# Main.net
KiCad netlist of a schematic drawn in Altium Designer
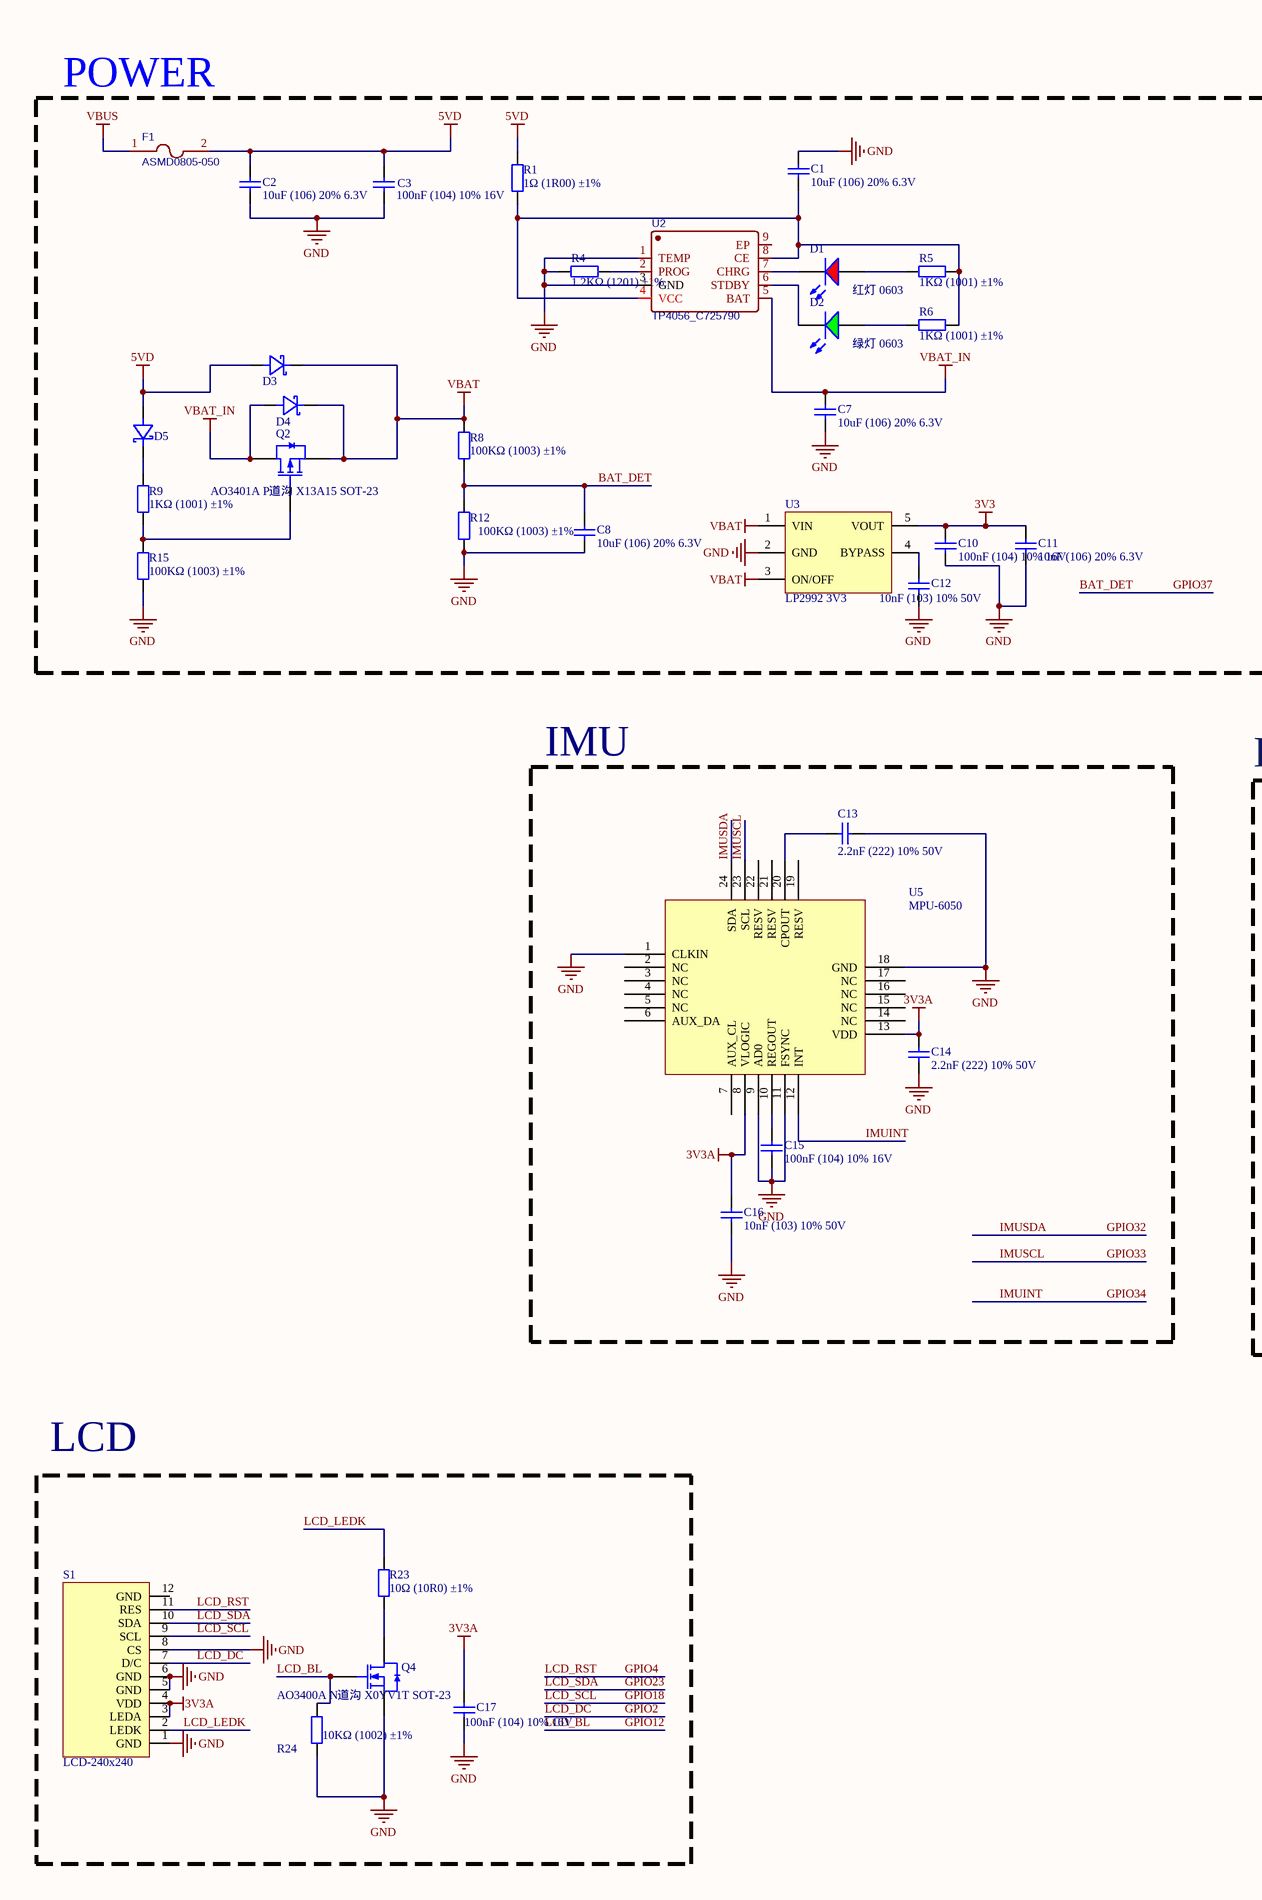
[diagram p0: Main.SchDoc, left]
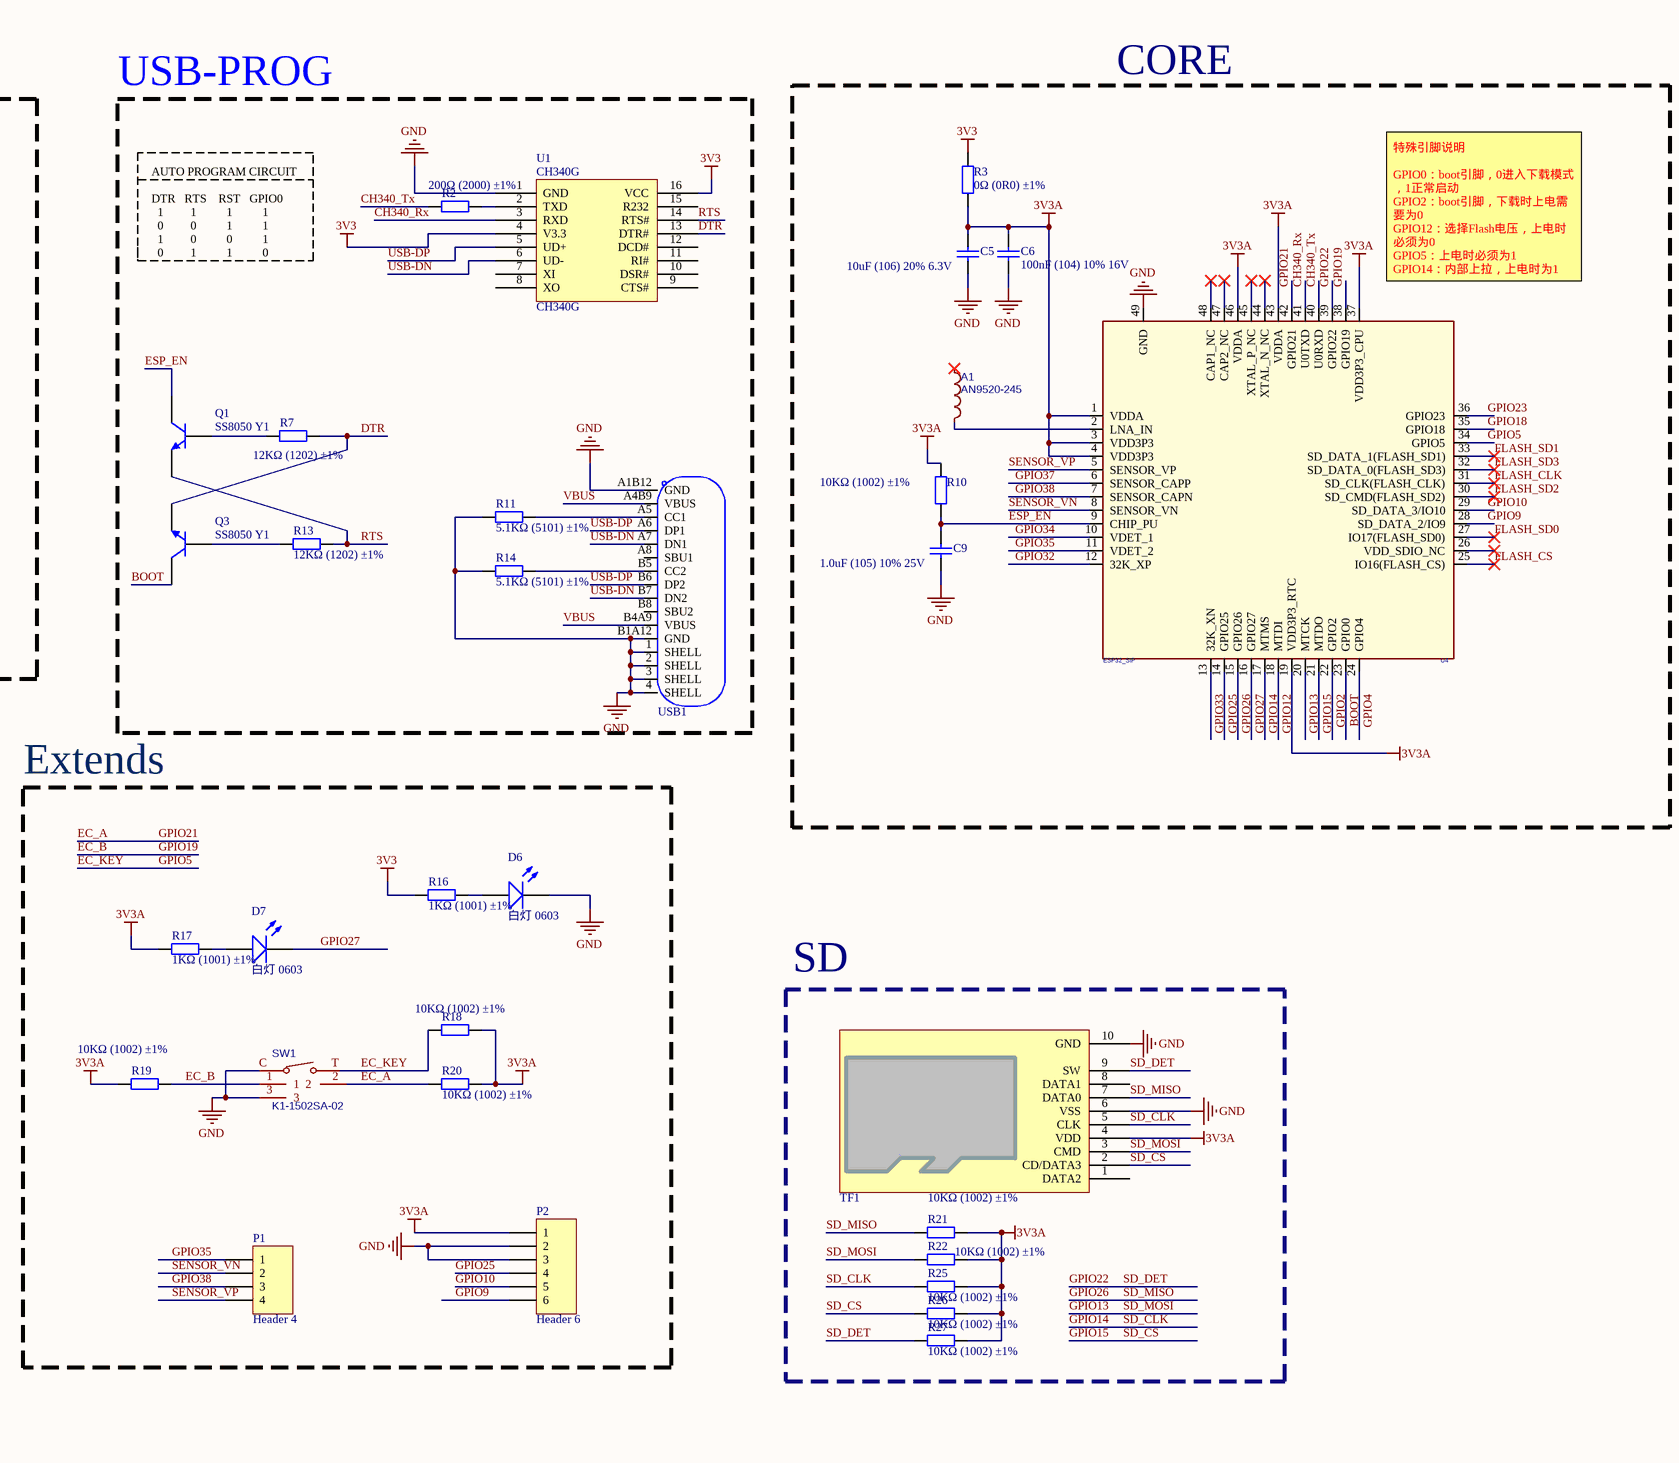
[diagram p1: Main.SchDoc, right]

(export (version "E")
  (design (tool "Eeschema 10.0.6"))
  (components
    (comp (ref "A1")
      (value "AN9520-245")
      (footprint "ANT-SMD_L9.5-W2.1")
      (description "陶瓷wifi/bt天线")
      (fields (field (name "BOM_SUPPLIER PART") "C99665"))
      (libsource (lib "mysch") (part "AN9520-245"))
    )
    (comp (ref "C1")
      (value "10uF (106) 20% 6.3V")
      (footprint "0402_C")
      (description "贴片电容")
      (libsource (lib "Miscellaneous Devices LC") (part "0402 10uF (106) 20% 6.3V"))
    )
    (comp (ref "C2")
      (value "10uF (106) 20% 6.3V")
      (footprint "0402_C")
      (description "贴片电容")
      (libsource (lib "Cap") (part "0402 10uF (106) 20% 6.3V"))
    )
    (comp (ref "C3")
      (value "100nF (104) 10% 16V")
      (footprint "0402_C")
      (description "贴片电容")
      (libsource (lib "Cap") (part "0402 100nF (104) 10% 16V"))
    )
    (comp (ref "C5")
      (value "10uF (106) 20% 6.3V")
      (footprint "0402_C")
      (description "贴片电容")
      (libsource (lib "Miscellaneous Devices LC") (part "0402 10uF (106) 20% 6.3V"))
    )
    (comp (ref "C6")
      (value "100nF (104) 10% 16V")
      (footprint "0402_C")
      (description "贴片电容")
      (libsource (lib "Miscellaneous Devices LC") (part "0402 100nF (104) 10% 16V"))
    )
    (comp (ref "C7")
      (value "10uF (106) 20% 6.3V")
      (footprint "0402_C")
      (description "贴片电容")
      (libsource (lib "Miscellaneous Devices LC") (part "0402 10uF (106) 20% 6.3V"))
    )
    (comp (ref "C8")
      (value "10uF (106) 20% 6.3V")
      (footprint "0402_C")
      (description "贴片电容")
      (libsource (lib "Miscellaneous Devices LC") (part "0402 10uF (106) 20% 6.3V"))
    )
    (comp (ref "C9")
      (value "1.0uF (105) 10% 25V")
      (footprint "0402_C")
      (description "贴片电容")
      (libsource (lib "Miscellaneous Devices LC") (part "0402 1.0uF (105) 10% 25V"))
    )
    (comp (ref "C10")
      (value "100nF (104) 10% 16V")
      (footprint "0402_C")
      (description "贴片电容")
      (libsource (lib "Miscellaneous Devices LC") (part "0402 100nF (104) 10% 16V"))
    )
    (comp (ref "C11")
      (value "10uF (106) 20% 6.3V")
      (footprint "0402_C")
      (description "贴片电容")
      (libsource (lib "Miscellaneous Devices LC") (part "0402 10uF (106) 20% 6.3V"))
    )
    (comp (ref "C12")
      (value "10nF (103) 10% 50V")
      (footprint "0402_C")
      (description "贴片电容")
      (libsource (lib "Miscellaneous Devices LC") (part "0402 10nF (103) 10% 50V"))
    )
    (comp (ref "C13")
      (value "2.2nF (222) 10% 50V")
      (footprint "0402_C")
      (description "贴片电容")
      (libsource (lib "Cap") (part "0402 2.2nF (222) 10% 50V"))
    )
    (comp (ref "C14")
      (value "2.2nF (222) 10% 50V")
      (footprint "0402_C")
      (description "贴片电容")
      (libsource (lib "Cap") (part "0402 2.2nF (222) 10% 50V"))
    )
    (comp (ref "C15")
      (value "100nF (104) 10% 16V")
      (footprint "0402_C")
      (description "贴片电容")
      (libsource (lib "Cap") (part "0402 100nF (104) 10% 16V"))
    )
    (comp (ref "C16")
      (value "10nF (103) 10% 50V")
      (footprint "0402_C")
      (description "贴片电容")
      (libsource (lib "Cap") (part "0402 10nF (103) 10% 50V"))
    )
    (comp (ref "C17")
      (value "100nF (104) 10% 16V")
      (footprint "0402_C")
      (description "贴片电容")
      (libsource (lib "Miscellaneous Devices LC") (part "0402 100nF (104) 10% 16V"))
    )
    (comp (ref "D1")
      (value "红灯 0603")
      (footprint "0603_LED_S1")
      (description "发光二极管")
      (libsource (lib "Miscellaneous Devices LC") (part "0603 红灯"))
    )
    (comp (ref "D2")
      (value "绿灯 0603")
      (footprint "0603_LED_S1")
      (description "发光二极管")
      (libsource (lib "Miscellaneous Devices LC") (part "0603 绿灯"))
    )
    (comp (ref "D3")
      (value "1N5819W")
      (footprint "SOD-123")
      (description "二极管")
      (fields (field (name "MANUFACTURER") "TWGMC(台湾迪嘉)"))
      (libsource (lib "mysch") (part "1N5819W"))
    )
    (comp (ref "D4")
      (value "1N5819W")
      (footprint "SOD-123")
      (description "二极管")
      (fields (field (name "MANUFACTURER") "TWGMC(台湾迪嘉)"))
      (libsource (lib "mysch") (part "1N5819W"))
    )
    (comp (ref "D5")
      (value "1N5819W")
      (footprint "SOD-123")
      (description "二极管")
      (fields (field (name "MANUFACTURER") "TWGMC(台湾迪嘉)"))
      (libsource (lib "mysch") (part "1N5819W"))
    )
    (comp (ref "D6")
      (value "白灯 0603")
      (footprint "0603_LED_S1")
      (description "发光二极管")
      (libsource (lib "Miscellaneous Devices LC") (part "0603 白灯"))
    )
    (comp (ref "D7")
      (value "白灯 0603")
      (footprint "0603_LED_S1")
      (description "发光二极管")
      (libsource (lib "Miscellaneous Devices LC") (part "0603 白灯"))
    )
    (comp (ref "F1")
      (value "ASMD0805-050")
      (footprint "ASMD0805")
      (fields (field (name "BOM_SUPPLIER PART") "C135329") (field (name "CONTRIBUTOR") "LCSC"))
      (libsource (lib "mysch") (part "ASMD0805-050"))
    )
    (comp (ref "P1")
      (value "Header 4")
      (footprint "HDR1X4")
      (description "Header, 4-Pin")
      (fields (field (name "PUBLISHER") "Altium Limited"))
      (libsource (lib "Miscellaneous Connectors") (part "Header 4"))
    )
    (comp (ref "P2")
      (value "Header 6")
      (footprint "HDR1X6")
      (description "Header, 6-Pin")
      (fields (field (name "PUBLISHER") "Altium Limited"))
      (libsource (lib "Miscellaneous Connectors") (part "Header 6"))
    )
    (comp (ref "Q1")
      (value "SS8050 Y1")
      (footprint "SOT-23(SOT-23-3)")
      (description "三极管")
      (libsource (lib "Miscellaneous Devices LC") (part "SOT-23 SS8050 Y1"))
    )
    (comp (ref "Q2")
      (value "AO3401A P道沟 X13A15 SOT-23")
      (footprint "SOT-23-3L")
      (description "MOS(场效应管)")
      (libsource (lib "Miscellaneous Devices LC") (part "AO3401A P道沟 X13A15 SOT-23"))
    )
    (comp (ref "Q3")
      (value "SS8050 Y1")
      (footprint "SOT-23(SOT-23-3)")
      (description "三极管")
      (libsource (lib "Miscellaneous Devices LC") (part "SOT-23 SS8050 Y1"))
    )
    (comp (ref "Q4")
      (value "AO3400A N道沟 X0YV1T SOT-23")
      (footprint "SOT-23-3L")
      (description "MOS(场效应管)")
      (libsource (lib "Miscellaneous Devices LC") (part "AO3400A N道沟 X0YV1T SOT-23"))
    )
    (comp (ref "R1")
      (value "1Ω (1R00) ±1%")
      (footprint "0402_R")
      (description "贴片电阻")
      (libsource (lib "Miscellaneous Devices LC") (part "0402 1Ω (1R00) 1%"))
    )
    (comp (ref "R2")
      (value "200Ω (2000) ±1%")
      (footprint "0402_R")
      (description "贴片电阻")
      (libsource (lib "Miscellaneous Devices LC") (part "0402 200Ω (2000) 1%"))
    )
    (comp (ref "R3")
      (value "0Ω (0R0) ±1%")
      (footprint "0402_R")
      (description "贴片电阻")
      (libsource (lib "Miscellaneous Devices LC") (part "0402 0Ω (0R0) 1%"))
    )
    (comp (ref "R4")
      (value "1.2KΩ (1201) ±1%")
      (footprint "0402_R")
      (description "贴片电阻")
      (libsource (lib "Miscellaneous Devices LC") (part "0402 1.2KΩ (1201) 1%"))
    )
    (comp (ref "R5")
      (value "1KΩ (1001) ±1%")
      (footprint "0402_R")
      (description "贴片电阻")
      (libsource (lib "") (part "0402 1KΩ (1001) 1%_1"))
    )
    (comp (ref "R6")
      (value "1KΩ (1001) ±1%")
      (footprint "0402_R")
      (description "贴片电阻")
      (libsource (lib "") (part "0402 1KΩ (1001) 1%_1"))
    )
    (comp (ref "R7")
      (value "12KΩ (1202) ±1%")
      (footprint "0402_R")
      (description "贴片电阻")
      (libsource (lib "RES") (part "0402 12KΩ (1202) 1%"))
    )
    (comp (ref "R8")
      (value "100KΩ (1003) ±1%")
      (footprint "0402_R")
      (description "贴片电阻")
      (libsource (lib "Miscellaneous Devices LC") (part "0402 100KΩ (1003) 1%"))
    )
    (comp (ref "R9")
      (value "1KΩ (1001) ±1%")
      (footprint "0402_R")
      (description "贴片电阻")
      (libsource (lib "Miscellaneous Devices LC") (part "0402 1KΩ (1001) 1%"))
    )
    (comp (ref "R10")
      (value "10KΩ (1002) ±1%")
      (footprint "0402_R")
      (description "贴片电阻")
      (libsource (lib "") (part "0402 10KΩ (1002) 1%_1"))
    )
    (comp (ref "R11")
      (value "5.1KΩ (5101) ±1%")
      (footprint "0402_R")
      (description "贴片电阻")
      (libsource (lib "RES") (part "0402 5.1KΩ (5101) 1%"))
    )
    (comp (ref "R12")
      (value "100KΩ (1003) ±1%")
      (footprint "0402_R")
      (description "贴片电阻")
      (libsource (lib "Miscellaneous Devices LC") (part "0402 100KΩ (1003) 1%"))
    )
    (comp (ref "R13")
      (value "12KΩ (1202) ±1%")
      (footprint "0402_R")
      (description "贴片电阻")
      (libsource (lib "RES") (part "0402 12KΩ (1202) 1%"))
    )
    (comp (ref "R14")
      (value "5.1KΩ (5101) ±1%")
      (footprint "0402_R")
      (description "贴片电阻")
      (libsource (lib "RES") (part "0402 5.1KΩ (5101) 1%"))
    )
    (comp (ref "R15")
      (value "100KΩ (1003) ±1%")
      (footprint "0402_R")
      (description "贴片电阻")
      (libsource (lib "Miscellaneous Devices LC") (part "0402 100KΩ (1003) 1%"))
    )
    (comp (ref "R16")
      (value "1KΩ (1001) ±1%")
      (footprint "0402_R")
      (description "贴片电阻")
      (libsource (lib "RES") (part "0402 1KΩ (1001) 1%"))
    )
    (comp (ref "R17")
      (value "1KΩ (1001) ±1%")
      (footprint "0402_R")
      (description "贴片电阻")
      (libsource (lib "RES") (part "0402 1KΩ (1001) 1%"))
    )
    (comp (ref "R18")
      (value "10KΩ (1002) ±1%")
      (footprint "0402_R")
      (description "贴片电阻")
      (libsource (lib "Miscellaneous Devices LC") (part "0402 10KΩ (1002) 1%"))
    )
    (comp (ref "R19")
      (value "10KΩ (1002) ±1%")
      (footprint "0402_R")
      (description "贴片电阻")
      (libsource (lib "Miscellaneous Devices LC") (part "0402 10KΩ (1002) 1%"))
    )
    (comp (ref "R20")
      (value "10KΩ (1002) ±1%")
      (footprint "0402_R")
      (description "贴片电阻")
      (libsource (lib "Miscellaneous Devices LC") (part "0402 10KΩ (1002) 1%"))
    )
    (comp (ref "R21")
      (value "10KΩ (1002) ±1%")
      (footprint "0402_R")
      (description "贴片电阻")
      (libsource (lib "Miscellaneous Devices LC") (part "0402 10KΩ (1002) 1%"))
    )
    (comp (ref "R22")
      (value "10KΩ (1002) ±1%")
      (footprint "0402_R")
      (description "贴片电阻")
      (libsource (lib "Miscellaneous Devices LC") (part "0402 10KΩ (1002) 1%"))
    )
    (comp (ref "R23")
      (value "10Ω (10R0) ±1%")
      (footprint "0402_R")
      (description "贴片电阻")
      (libsource (lib "Miscellaneous Devices LC") (part "0402 10Ω (10R0) 1%"))
    )
    (comp (ref "R24")
      (value "10KΩ (1002) ±1%")
      (footprint "0402_R")
      (description "贴片电阻")
      (libsource (lib "") (part "0402 10KΩ (1002) 1%_1"))
    )
    (comp (ref "R25")
      (value "10KΩ (1002) ±1%")
      (footprint "0402_R")
      (description "贴片电阻")
      (libsource (lib "Miscellaneous Devices LC") (part "0402 10KΩ (1002) 1%"))
    )
    (comp (ref "R26")
      (value "10KΩ (1002) ±1%")
      (footprint "0402_R")
      (description "贴片电阻")
      (libsource (lib "Miscellaneous Devices LC") (part "0402 10KΩ (1002) 1%"))
    )
    (comp (ref "R27")
      (value "10KΩ (1002) ±1%")
      (footprint "0402_R")
      (description "贴片电阻")
      (libsource (lib "Miscellaneous Devices LC") (part "0402 10KΩ (1002) 1%"))
    )
    (comp (ref "S1")
      (value "LCD-240x240")
      (footprint "LCD-240x240-FlUSH-154")
      (description "显示屏")
      (libsource (lib "mLib") (part "LCD-240x240"))
    )
    (comp (ref "SW1")
      (value "K1-1502SA-02")
      (footprint "KEY-SMD_K1-1502SA-02")
      (description "拨码开关")
      (fields (field (name "BOM_SUPPLIER PART") "C128929") (field (name "CONTRIBUTOR") "LCSC"))
      (libsource (lib "mysch") (part "K1-1502SA-02"))
    )
    (comp (ref "TF1")
      (value "TF")
      (footprint "TF-SMD_THD2528")
      (description "8脚自弹")
      (libsource (lib "mysch") (part "TF卡座"))
    )
    (comp (ref "U1")
      (value "CH340G")
      (footprint "SOIC-16_150mil")
      (description "USB")
      (libsource (lib "Miscellaneous Devices LC") (part "CH340G_[C14267]"))
    )
    (comp (ref "U2")
      (value "TP4056_C725790")
      (footprint "ESOP-8_TP4056")
      (fields
        (field (name "BOM_SUPPLIER PART") "C725790")
        (field (name "BOM_MANUFACTURER PART") "TP4056")
        (field (name "CONTRIBUTOR") "LCSC")
      )
      (libsource (lib "mysch") (part "TP4056"))
    )
    (comp (ref "U3")
      (value "LP2992 3V3")
      (footprint "SOT-23-5_L3.0-W1.7-P0.95-LS2.8-BL")
      (description "LDO")
      (libsource (lib "mLib") (part "LP2992"))
    )
    (comp (ref "U4")
      (value "ESP32_SIP")
      (footprint "QFN-48_7X7")
      (libsource (lib "mLib") (part "ESP32-PICO"))
    )
    (comp (ref "U5")
      (value "MPU-6050")
      (footprint "QFN-24_4x4x05P")
      (description "传感器")
      (libsource (lib "IC") (part "MPU-6050_[C24112]"))
    )
    (comp (ref "USB1")
      (value "TYPE-C16PIN")
      (footprint "TYPE-C-SMD")
      (fields (field (name "MANUFACTURER") "SHOU HAN(首韩)"))
      (libsource (lib "mysch") (part "TYPE-C16PIN"))
    )
  )
  (nets
    (net (code "1") (name "/BAT_DET") (class "Default")
      (node (ref "C8") (pin "2") (pinfunction "2_2") (pintype "passive"))
      (node (ref "R12") (pin "2") (pinfunction "2_2") (pintype "passive"))
      (node (ref "R8") (pin "1") (pinfunction "1_1") (pintype "passive"))
      (node (ref "U4") (pin "6") (pinfunction "SENSOR_CAPP_6") (pintype "passive"))
    )
    (net (code "2") (name "/BOOT") (class "Default")
      (node (ref "Q3") (pin "3") (pinfunction "C_3") (pintype "passive"))
      (node (ref "U4") (pin "23") (pinfunction "GPIO0_23") (pintype "passive"))
    )
    (net (code "3") (name "/CH340_Rx") (class "Default")
      (node (ref "U1") (pin "3") (pinfunction "RXD_3") (pintype "passive"))
      (node (ref "U4") (pin "41") (pinfunction "U0TXD_41") (pintype "power_in"))
    )
    (net (code "4") (name "/CH340_Tx") (class "Default")
      (node (ref "R2") (pin "1") (pinfunction "1_1") (pintype "passive"))
      (node (ref "U4") (pin "40") (pinfunction "U0RXD_40") (pintype "power_in"))
    )
    (net (code "5") (name "/DTR") (class "Default")
      (node (ref "Q3") (pin "2") (pinfunction "E_2") (pintype "passive"))
      (node (ref "R7") (pin "2") (pinfunction "2_2") (pintype "passive"))
      (node (ref "U1") (pin "13") (pinfunction "DTR#_13") (pintype "passive"))
    )
    (net (code "6") (name "/EC_A") (class "Default")
      (node (ref "R20") (pin "1") (pinfunction "1_1") (pintype "passive"))
      (node (ref "SW1") (pin "2") (pinfunction "2_2") (pintype "passive"))
      (node (ref "U4") (pin "42") (pinfunction "GPIO21_42") (pintype "passive"))
    )
    (net (code "7") (name "/EC_B") (class "Default")
      (node (ref "R19") (pin "2") (pinfunction "2_2") (pintype "passive"))
      (node (ref "SW1") (pin "1") (pinfunction "1_1") (pintype "passive"))
      (node (ref "U4") (pin "38") (pinfunction "GPIO19_38") (pintype "passive"))
    )
    (net (code "8") (name "/EC_KEY") (class "Default")
      (node (ref "R18") (pin "1") (pinfunction "1_1") (pintype "passive"))
      (node (ref "SW1") (pin "T") (pinfunction "T_T") (pintype "passive"))
      (node (ref "U4") (pin "34") (pinfunction "GPIO5_34") (pintype "passive"))
    )
    (net (code "9") (name "/ESP_EN") (class "Default")
      (node (ref "C9") (pin "2") (pinfunction "2_2") (pintype "passive"))
      (node (ref "Q1") (pin "3") (pinfunction "C_3") (pintype "passive"))
      (node (ref "R10") (pin "1") (pinfunction "1_1") (pintype "passive"))
      (node (ref "U4") (pin "9") (pinfunction "CHIP_PU_9") (pintype "passive"))
    )
    (net (code "10") (name "/FLASH_CLK") (class "Default")
      (node (ref "U4") (pin "31") (pinfunction "SD_CLK(FLASH_CLK)_31") (pintype "passive+no_connect"))
    )
    (net (code "11") (name "/FLASH_CS") (class "Default")
      (node (ref "U4") (pin "25") (pinfunction "IO16(FLASH_CS)_25") (pintype "passive+no_connect"))
    )
    (net (code "12") (name "/FLASH_SD0") (class "Default")
      (node (ref "U4") (pin "27") (pinfunction "IO17(FLASH_SD0)_27") (pintype "passive+no_connect"))
    )
    (net (code "13") (name "/FLASH_SD1") (class "Default")
      (node (ref "U4") (pin "33") (pinfunction "SD_DATA_1(FLASH_SD1)_33") (pintype "passive+no_connect"))
    )
    (net (code "14") (name "/FLASH_SD2") (class "Default")
      (node (ref "U4") (pin "30") (pinfunction "SD_CMD(FLASH_SD2)_30") (pintype "passive+no_connect"))
    )
    (net (code "15") (name "/FLASH_SD3") (class "Default")
      (node (ref "U4") (pin "32") (pinfunction "SD_DATA_0(FLASH_SD3)_32") (pintype "passive+no_connect"))
    )
    (net (code "16") (name "/GPIO2") (class "Default")
      (node (ref "S1") (pin "7") (pinfunction "D/C_7") (pintype "passive"))
      (node (ref "U4") (pin "22") (pinfunction "GPIO2_22") (pintype "passive"))
    )
    (net (code "17") (name "/GPIO4") (class "Default")
      (node (ref "S1") (pin "11") (pinfunction "RES_11") (pintype "passive"))
      (node (ref "U4") (pin "24") (pinfunction "GPIO4_24") (pintype "passive"))
    )
    (net (code "18") (name "/GPIO9") (class "Default")
      (node (ref "P2") (pin "6") (pinfunction "6_6") (pintype "passive"))
      (node (ref "U4") (pin "28") (pinfunction "SD_DATA_2/IO9_28") (pintype "passive"))
    )
    (net (code "19") (name "/GPIO10") (class "Default")
      (node (ref "P2") (pin "5") (pinfunction "5_5") (pintype "passive"))
      (node (ref "U4") (pin "29") (pinfunction "SD_DATA_3/IO10_29") (pintype "passive"))
    )
    (net (code "20") (name "/GPIO12") (class "Default")
      (node (ref "Q4") (pin "1") (pinfunction "G_1") (pintype "passive"))
      (node (ref "R24") (pin "2") (pinfunction "2_2") (pintype "passive"))
      (node (ref "U4") (pin "18") (pinfunction "MTDI_18") (pintype "passive"))
    )
    (net (code "21") (name "/GPIO13") (class "Default")
      (node (ref "R22") (pin "1") (pinfunction "1_1") (pintype "passive"))
      (node (ref "TF1") (pin "3") (pinfunction "CMD_3") (pintype "passive"))
      (node (ref "U4") (pin "20") (pinfunction "MTCK_20") (pintype "passive"))
    )
    (net (code "22") (name "/GPIO14") (class "Default")
      (node (ref "R25") (pin "1") (pinfunction "1_1") (pintype "passive"))
      (node (ref "TF1") (pin "5") (pinfunction "CLK_5") (pintype "passive"))
      (node (ref "U4") (pin "17") (pinfunction "MTMS_17") (pintype "passive"))
    )
    (net (code "23") (name "/GPIO15") (class "Default")
      (node (ref "R26") (pin "1") (pinfunction "1_1") (pintype "passive"))
      (node (ref "TF1") (pin "2") (pinfunction "CD/DATA3_2") (pintype "passive"))
      (node (ref "U4") (pin "21") (pinfunction "MTDO_21") (pintype "passive"))
    )
    (net (code "24") (name "/GPIO18") (class "Default")
      (node (ref "S1") (pin "9") (pinfunction "SCL_9") (pintype "passive"))
      (node (ref "U4") (pin "35") (pinfunction "GPIO18_35") (pintype "passive"))
    )
    (net (code "25") (name "/GPIO22") (class "Default")
      (node (ref "R27") (pin "1") (pinfunction "1_1") (pintype "passive"))
      (node (ref "TF1") (pin "9") (pinfunction "SW_9") (pintype "passive"))
      (node (ref "U4") (pin "39") (pinfunction "GPIO22_39") (pintype "passive"))
    )
    (net (code "26") (name "/GPIO23") (class "Default")
      (node (ref "S1") (pin "10") (pinfunction "SDA_10") (pintype "passive"))
      (node (ref "U4") (pin "36") (pinfunction "GPIO23_36") (pintype "passive"))
    )
    (net (code "27") (name "/GPIO25") (class "Default")
      (node (ref "P2") (pin "4") (pinfunction "4_4") (pintype "passive"))
      (node (ref "U4") (pin "14") (pinfunction "GPIO25_14") (pintype "passive"))
    )
    (net (code "28") (name "/GPIO26") (class "Default")
      (node (ref "R21") (pin "1") (pinfunction "1_1") (pintype "passive"))
      (node (ref "TF1") (pin "7") (pinfunction "DATA0_7") (pintype "passive"))
      (node (ref "U4") (pin "15") (pinfunction "GPIO26_15") (pintype "passive"))
    )
    (net (code "29") (name "/GPIO27") (class "Default")
      (node (ref "D7") (pin "K") (pinfunction "K_K") (pintype "passive"))
      (node (ref "U4") (pin "16") (pinfunction "GPIO27_16") (pintype "passive"))
    )
    (net (code "30") (name "/GPIO32") (class "Default")
      (node (ref "U4") (pin "12") (pinfunction "32K_XP_12") (pintype "passive"))
      (node (ref "U5") (pin "24") (pinfunction "SDA_24") (pintype "passive"))
    )
    (net (code "31") (name "/GPIO33") (class "Default")
      (node (ref "U4") (pin "13") (pinfunction "32K_XN_13") (pintype "passive"))
      (node (ref "U5") (pin "23") (pinfunction "SCL_23") (pintype "passive"))
    )
    (net (code "32") (name "/GPIO34") (class "Default")
      (node (ref "U4") (pin "10") (pinfunction "VDET_1_10") (pintype "passive"))
      (node (ref "U5") (pin "12") (pinfunction "INT_12") (pintype "passive"))
    )
    (net (code "33") (name "/GPIO35") (class "Default")
      (node (ref "P1") (pin "1") (pinfunction "1_1") (pintype "passive"))
      (node (ref "U4") (pin "11") (pinfunction "VDET_2_11") (pintype "passive"))
    )
    (net (code "34") (name "/GPIO38") (class "Default")
      (node (ref "P1") (pin "3") (pinfunction "3_3") (pintype "passive"))
      (node (ref "U4") (pin "7") (pinfunction "SENSOR_CAPN_7") (pintype "passive"))
    )
    (net (code "35") (name "/LCD_LEDK") (class "Default")
      (node (ref "R23") (pin "2") (pinfunction "2_2") (pintype "passive"))
      (node (ref "S1") (pin "2") (pinfunction "LEDK_2") (pintype "passive"))
    )
    (net (code "36") (name "/RTS") (class "Default")
      (node (ref "Q1") (pin "2") (pinfunction "E_2") (pintype "passive"))
      (node (ref "R13") (pin "2") (pinfunction "2_2") (pintype "passive"))
      (node (ref "U1") (pin "14") (pinfunction "RTS#_14") (pintype "passive"))
    )
    (net (code "37") (name "/SENSOR_VN") (class "Default")
      (node (ref "P1") (pin "2") (pinfunction "2_2") (pintype "passive"))
      (node (ref "U4") (pin "8") (pinfunction "SENSOR_VN_8") (pintype "passive"))
    )
    (net (code "38") (name "/SENSOR_VP") (class "Default")
      (node (ref "P1") (pin "4") (pinfunction "4_4") (pintype "passive"))
      (node (ref "U4") (pin "5") (pinfunction "SENSOR_VP_5") (pintype "passive"))
    )
    (net (code "39") (name "/USB-DN") (class "Default")
      (node (ref "U1") (pin "6") (pinfunction "UD-_6") (pintype "passive"))
      (node (ref "USB1") (pin "A7") (pinfunction "DN1_A7") (pintype "passive"))
      (node (ref "USB1") (pin "B7") (pinfunction "DN2_B7") (pintype "passive"))
    )
    (net (code "40") (name "/USB-DP") (class "Default")
      (node (ref "U1") (pin "5") (pinfunction "UD+_5") (pintype "passive"))
      (node (ref "USB1") (pin "A6") (pinfunction "DP1_A6") (pintype "passive"))
      (node (ref "USB1") (pin "B6") (pinfunction "DP2_B6") (pintype "passive"))
    )
    (net (code "41") (name "3V3") (class "Default")
      (node (ref "C10") (pin "2") (pinfunction "2_2") (pintype "passive"))
      (node (ref "C11") (pin "2") (pinfunction "2_2") (pintype "passive"))
      (node (ref "R16") (pin "1") (pinfunction "1_1") (pintype "passive"))
      (node (ref "R3") (pin "2") (pinfunction "2_2") (pintype "passive"))
      (node (ref "U1") (pin "16") (pinfunction "VCC_16") (pintype "passive"))
      (node (ref "U1") (pin "4") (pinfunction "V3.3_4") (pintype "passive"))
      (node (ref "U3") (pin "5") (pinfunction "VOUT_5") (pintype "passive"))
    )
    (net (code "42") (name "3V3A") (class "Default")
      (node (ref "C14") (pin "2") (pinfunction "2_2") (pintype "passive"))
      (node (ref "C16") (pin "2") (pinfunction "2_2") (pintype "passive"))
      (node (ref "C17") (pin "2") (pinfunction "2_2") (pintype "passive"))
      (node (ref "C5") (pin "2") (pinfunction "2_2") (pintype "passive"))
      (node (ref "C6") (pin "2") (pinfunction "2_2") (pintype "passive"))
      (node (ref "P2") (pin "1") (pinfunction "1_1") (pintype "passive"))
      (node (ref "R10") (pin "2") (pinfunction "2_2") (pintype "passive"))
      (node (ref "R17") (pin "1") (pinfunction "1_1") (pintype "passive"))
      (node (ref "R18") (pin "2") (pinfunction "2_2") (pintype "passive"))
      (node (ref "R19") (pin "1") (pinfunction "1_1") (pintype "passive"))
      (node (ref "R20") (pin "2") (pinfunction "2_2") (pintype "passive"))
      (node (ref "R21") (pin "2") (pinfunction "2_2") (pintype "passive"))
      (node (ref "R22") (pin "2") (pinfunction "2_2") (pintype "passive"))
      (node (ref "R25") (pin "2") (pinfunction "2_2") (pintype "passive"))
      (node (ref "R26") (pin "2") (pinfunction "2_2") (pintype "passive"))
      (node (ref "R27") (pin "2") (pinfunction "2_2") (pintype "passive"))
      (node (ref "R3") (pin "1") (pinfunction "1_1") (pintype "passive"))
      (node (ref "S1") (pin "3") (pinfunction "LEDA_3") (pintype "passive"))
      (node (ref "S1") (pin "4") (pinfunction "VDD_4") (pintype "passive"))
      (node (ref "TF1") (pin "4") (pinfunction "VDD_4") (pintype "passive"))
      (node (ref "U4") (pin "1") (pinfunction "VDDA_1") (pintype "power_in"))
      (node (ref "U4") (pin "19") (pinfunction "VDD3P3_RTC_19") (pintype "power_in"))
      (node (ref "U4") (pin "3") (pinfunction "VDD3P3_3") (pintype "power_in"))
      (node (ref "U4") (pin "37") (pinfunction "VDD3P3_CPU_37") (pintype "power_in"))
      (node (ref "U4") (pin "4") (pinfunction "VDD3P3_4") (pintype "power_in"))
      (node (ref "U4") (pin "43") (pinfunction "VDDA_43") (pintype "power_in"))
      (node (ref "U4") (pin "46") (pinfunction "VDDA_46") (pintype "power_in"))
      (node (ref "U5") (pin "13") (pinfunction "VDD_13") (pintype "passive"))
      (node (ref "U5") (pin "8") (pinfunction "VLOGIC_8") (pintype "passive"))
    )
    (net (code "43") (name "5VD") (class "Default")
      (node (ref "C2") (pin "2") (pinfunction "2_2") (pintype "passive"))
      (node (ref "C3") (pin "2") (pinfunction "2_2") (pintype "passive"))
      (node (ref "D3") (pin "2") (pinfunction "A_2") (pintype "passive"))
      (node (ref "D5") (pin "2") (pinfunction "A_2") (pintype "passive"))
      (node (ref "F1") (pin "2") (pinfunction "2_2") (pintype "passive"))
      (node (ref "R1") (pin "1") (pinfunction "1_1") (pintype "passive"))
    )
    (net (code "44") (name "GND") (class "Default")
      (node (ref "C1") (pin "2") (pinfunction "2_2") (pintype "passive"))
      (node (ref "C10") (pin "1") (pinfunction "1_1") (pintype "passive"))
      (node (ref "C11") (pin "1") (pinfunction "1_1") (pintype "passive"))
      (node (ref "C12") (pin "1") (pinfunction "1_1") (pintype "passive"))
      (node (ref "C13") (pin "2") (pinfunction "2_2") (pintype "passive"))
      (node (ref "C14") (pin "1") (pinfunction "1_1") (pintype "passive"))
      (node (ref "C15") (pin "1") (pinfunction "1_1") (pintype "passive"))
      (node (ref "C16") (pin "1") (pinfunction "1_1") (pintype "passive"))
      (node (ref "C17") (pin "1") (pinfunction "1_1") (pintype "passive"))
      (node (ref "C2") (pin "1") (pinfunction "1_1") (pintype "passive"))
      (node (ref "C3") (pin "1") (pinfunction "1_1") (pintype "passive"))
      (node (ref "C5") (pin "1") (pinfunction "1_1") (pintype "passive"))
      (node (ref "C6") (pin "1") (pinfunction "1_1") (pintype "passive"))
      (node (ref "C7") (pin "1") (pinfunction "1_1") (pintype "passive"))
      (node (ref "C8") (pin "1") (pinfunction "1_1") (pintype "passive"))
      (node (ref "C9") (pin "1") (pinfunction "1_1") (pintype "passive"))
      (node (ref "D6") (pin "K") (pinfunction "K_K") (pintype "passive"))
      (node (ref "P2") (pin "2") (pinfunction "2_2") (pintype "passive"))
      (node (ref "P2") (pin "3") (pinfunction "3_3") (pintype "passive"))
      (node (ref "Q4") (pin "2") (pinfunction "S_2") (pintype "passive"))
      (node (ref "R11") (pin "1") (pinfunction "1_1") (pintype "passive"))
      (node (ref "R12") (pin "1") (pinfunction "1_1") (pintype "passive"))
      (node (ref "R14") (pin "1") (pinfunction "1_1") (pintype "passive"))
      (node (ref "R15") (pin "1") (pinfunction "1_1") (pintype "passive"))
      (node (ref "R24") (pin "1") (pinfunction "1_1") (pintype "passive"))
      (node (ref "R4") (pin "1") (pinfunction "1_1") (pintype "passive"))
      (node (ref "S1") (pin "1") (pinfunction "GND_1") (pintype "passive"))
      (node (ref "S1") (pin "5") (pinfunction "GND_5") (pintype "passive"))
      (node (ref "S1") (pin "6") (pinfunction "GND_6") (pintype "passive"))
      (node (ref "S1") (pin "8") (pinfunction "CS_8") (pintype "passive"))
      (node (ref "SW1") (pin "3") (pinfunction "3_3") (pintype "passive"))
      (node (ref "SW1") (pin "C") (pinfunction "C_C") (pintype "passive"))
      (node (ref "TF1") (pin "10") (pinfunction "GND_10") (pintype "passive"))
      (node (ref "TF1") (pin "6") (pinfunction "VSS_6") (pintype "passive"))
      (node (ref "U1") (pin "1") (pinfunction "GND_1") (pintype "passive"))
      (node (ref "U2") (pin "1") (pinfunction "TEMP_1") (pintype "passive"))
      (node (ref "U2") (pin "3") (pinfunction "GND_3") (pintype "passive"))
      (node (ref "U3") (pin "2") (pinfunction "GND_2") (pintype "passive"))
      (node (ref "U4") (pin "49") (pinfunction "GND_49") (pintype "power_in"))
      (node (ref "U5") (pin "1") (pinfunction "CLKIN_1") (pintype "passive"))
      (node (ref "U5") (pin "11") (pinfunction "FSYNC_11") (pintype "passive"))
      (node (ref "U5") (pin "18") (pinfunction "GND_18") (pintype "passive"))
      (node (ref "U5") (pin "9") (pinfunction "AD0_9") (pintype "passive"))
      (node (ref "USB1") (pin "1") (pinfunction "SHELL_1") (pintype "passive"))
      (node (ref "USB1") (pin "2") (pinfunction "SHELL_2") (pintype "passive"))
      (node (ref "USB1") (pin "3") (pinfunction "SHELL_3") (pintype "passive"))
      (node (ref "USB1") (pin "4") (pinfunction "SHELL_4") (pintype "passive"))
      (node (ref "USB1") (pin "A1B12") (pinfunction "GND_A1B12") (pintype "passive"))
      (node (ref "USB1") (pin "B1A12") (pinfunction "GND_B1A12") (pintype "passive"))
    )
    (net (code "45") (name "Net-(D1-PadA)") (class "Default")
      (node (ref "D1") (pin "A") (pinfunction "A_A") (pintype "passive"))
      (node (ref "R5") (pin "1") (pinfunction "1_1") (pintype "passive"))
    )
    (net (code "46") (name "Net-(D2-PadA)") (class "Default")
      (node (ref "D2") (pin "A") (pinfunction "A_A") (pintype "passive"))
      (node (ref "R6") (pin "1") (pinfunction "1_1") (pintype "passive"))
    )
    (net (code "47") (name "Net-(D5-C)") (class "Default")
      (node (ref "D5") (pin "1") (pinfunction "C_1") (pintype "passive"))
      (node (ref "R9") (pin "2") (pinfunction "2_2") (pintype "passive"))
    )
    (net (code "48") (name "Net-(D6-PadA)") (class "Default")
      (node (ref "D6") (pin "A") (pinfunction "A_A") (pintype "passive"))
      (node (ref "R16") (pin "2") (pinfunction "2_2") (pintype "passive"))
    )
    (net (code "49") (name "Net-(D7-PadA)") (class "Default")
      (node (ref "D7") (pin "A") (pinfunction "A_A") (pintype "passive"))
      (node (ref "R17") (pin "2") (pinfunction "2_2") (pintype "passive"))
    )
    (net (code "50") (name "Net-(Q1-B)") (class "Default")
      (node (ref "Q1") (pin "1") (pinfunction "B_1") (pintype "passive"))
      (node (ref "R7") (pin "1") (pinfunction "1_1") (pintype "passive"))
    )
    (net (code "51") (name "Net-(Q2-G)") (class "Default")
      (node (ref "Q2") (pin "1") (pinfunction "G_1") (pintype "passive"))
      (node (ref "R15") (pin "2") (pinfunction "2_2") (pintype "passive"))
      (node (ref "R9") (pin "1") (pinfunction "1_1") (pintype "passive"))
    )
    (net (code "52") (name "Net-(Q3-B)") (class "Default")
      (node (ref "Q3") (pin "1") (pinfunction "B_1") (pintype "passive"))
      (node (ref "R13") (pin "1") (pinfunction "1_1") (pintype "passive"))
    )
    (net (code "53") (name "Net-(Q4-D)") (class "Default")
      (node (ref "Q4") (pin "3") (pinfunction "D_3") (pintype "passive"))
      (node (ref "R23") (pin "1") (pinfunction "1_1") (pintype "passive"))
    )
    (net (code "54") (name "Net-(U1-TXD)") (class "Default")
      (node (ref "R2") (pin "2") (pinfunction "2_2") (pintype "passive"))
      (node (ref "U1") (pin "2") (pinfunction "TXD_2") (pintype "passive"))
    )
    (net (code "55") (name "Net-(U2-CE)") (class "Default")
      (node (ref "C1") (pin "1") (pinfunction "1_1") (pintype "passive"))
      (node (ref "R1") (pin "2") (pinfunction "2_2") (pintype "passive"))
      (node (ref "R5") (pin "2") (pinfunction "2_2") (pintype "passive"))
      (node (ref "R6") (pin "2") (pinfunction "2_2") (pintype "passive"))
      (node (ref "U2") (pin "4") (pinfunction "VCC_4") (pintype "passive"))
      (node (ref "U2") (pin "8") (pinfunction "CE_8") (pintype "passive"))
    )
    (net (code "56") (name "Net-(U2-CHRG)") (class "Default")
      (node (ref "D1") (pin "K") (pinfunction "K_K") (pintype "passive"))
      (node (ref "U2") (pin "7") (pinfunction "CHRG_7") (pintype "passive"))
    )
    (net (code "57") (name "Net-(U2-PROG)") (class "Default")
      (node (ref "R4") (pin "2") (pinfunction "2_2") (pintype "passive"))
      (node (ref "U2") (pin "2") (pinfunction "PROG_2") (pintype "passive"))
    )
    (net (code "58") (name "Net-(U2-STDBY)") (class "Default")
      (node (ref "D2") (pin "K") (pinfunction "K_K") (pintype "passive"))
      (node (ref "U2") (pin "6") (pinfunction "STDBY_6") (pintype "passive"))
    )
    (net (code "59") (name "Net-(U3-BYPASS)") (class "Default")
      (node (ref "C12") (pin "2") (pinfunction "2_2") (pintype "passive"))
      (node (ref "U3") (pin "4") (pinfunction "BYPASS_4") (pintype "passive"))
    )
    (net (code "60") (name "Net-(U4-LNA_IN)") (class "Default")
      (node (ref "A1") (pin "2") (pinfunction "2_2") (pintype "passive"))
      (node (ref "U4") (pin "2") (pinfunction "LNA_IN_2") (pintype "passive"))
    )
    (net (code "61") (name "Net-(U5-CPOUT)") (class "Default")
      (node (ref "C13") (pin "1") (pinfunction "1_1") (pintype "passive"))
      (node (ref "U5") (pin "20") (pinfunction "CPOUT_20") (pintype "passive"))
    )
    (net (code "62") (name "Net-(U5-REGOUT)") (class "Default")
      (node (ref "C15") (pin "2") (pinfunction "2_2") (pintype "passive"))
      (node (ref "U5") (pin "10") (pinfunction "REGOUT_10") (pintype "passive"))
    )
    (net (code "63") (name "Net-(USB1-CC1)") (class "Default")
      (node (ref "R11") (pin "2") (pinfunction "2_2") (pintype "passive"))
      (node (ref "USB1") (pin "A5") (pinfunction "CC1_A5") (pintype "passive"))
    )
    (net (code "64") (name "Net-(USB1-CC2)") (class "Default")
      (node (ref "R14") (pin "2") (pinfunction "2_2") (pintype "passive"))
      (node (ref "USB1") (pin "B5") (pinfunction "CC2_B5") (pintype "passive"))
    )
    (net (code "65") (name "VBAT") (class "Default")
      (node (ref "D3") (pin "1") (pinfunction "C_1") (pintype "passive"))
      (node (ref "D4") (pin "1") (pinfunction "C_1") (pintype "passive"))
      (node (ref "Q2") (pin "2") (pinfunction "S_2") (pintype "passive"))
      (node (ref "R8") (pin "2") (pinfunction "2_2") (pintype "passive"))
      (node (ref "U3") (pin "1") (pinfunction "VIN_1") (pintype "passive"))
      (node (ref "U3") (pin "3") (pinfunction "ON/OFF_3") (pintype "passive"))
    )
    (net (code "66") (name "VBAT_IN") (class "Default")
      (node (ref "C7") (pin "2") (pinfunction "2_2") (pintype "passive"))
      (node (ref "D4") (pin "2") (pinfunction "A_2") (pintype "passive"))
      (node (ref "Q2") (pin "3") (pinfunction "D_3") (pintype "passive"))
      (node (ref "U2") (pin "5") (pinfunction "BAT_5") (pintype "passive"))
    )
    (net (code "67") (name "VBUS") (class "Default")
      (node (ref "F1") (pin "1") (pinfunction "1_1") (pintype "passive"))
      (node (ref "USB1") (pin "A4B9") (pinfunction "VBUS_A4B9") (pintype "passive"))
      (node (ref "USB1") (pin "B4A9") (pinfunction "VBUS_B4A9") (pintype "passive"))
    )
    (net (code "68") (name "unconnected-(A1-Pad1)") (class "Default")
      (node (ref "A1") (pin "1") (pinfunction "1_1") (pintype "passive+no_connect"))
    )
    (net (code "69") (name "unconnected-(S1-GND-Pad12)") (class "Default")
      (node (ref "S1") (pin "12") (pinfunction "GND_12") (pintype "passive"))
    )
    (net (code "70") (name "unconnected-(TF1-DATA1-Pad8)") (class "Default")
      (node (ref "TF1") (pin "8") (pinfunction "DATA1_8") (pintype "passive"))
    )
    (net (code "71") (name "unconnected-(TF1-DATA2-Pad1)") (class "Default")
      (node (ref "TF1") (pin "1") (pinfunction "DATA2_1") (pintype "passive"))
    )
    (net (code "72") (name "unconnected-(U1-CTS#-Pad9)") (class "Default")
      (node (ref "U1") (pin "9") (pinfunction "CTS#_9") (pintype "passive"))
    )
    (net (code "73") (name "unconnected-(U1-DCD#-Pad12)") (class "Default")
      (node (ref "U1") (pin "12") (pinfunction "DCD#_12") (pintype "passive"))
    )
    (net (code "74") (name "unconnected-(U1-DSR#-Pad10)") (class "Default")
      (node (ref "U1") (pin "10") (pinfunction "DSR#_10") (pintype "passive"))
    )
    (net (code "75") (name "unconnected-(U1-R232-Pad15)") (class "Default")
      (node (ref "U1") (pin "15") (pinfunction "R232_15") (pintype "passive"))
    )
    (net (code "76") (name "unconnected-(U1-RI#-Pad11)") (class "Default")
      (node (ref "U1") (pin "11") (pinfunction "RI#_11") (pintype "passive"))
    )
    (net (code "77") (name "unconnected-(U1-XI-Pad7)") (class "Default")
      (node (ref "U1") (pin "7") (pinfunction "XI_7") (pintype "passive"))
    )
    (net (code "78") (name "unconnected-(U1-XO-Pad8)") (class "Default")
      (node (ref "U1") (pin "8") (pinfunction "XO_8") (pintype "passive"))
    )
    (net (code "79") (name "unconnected-(U2-EP-Pad9)") (class "Default")
      (node (ref "U2") (pin "9") (pinfunction "EP_9") (pintype "passive"))
    )
    (net (code "80") (name "unconnected-(U4-CAP1_NC-Pad48)") (class "Default")
      (node (ref "U4") (pin "48") (pinfunction "CAP1_NC_48") (pintype "passive+no_connect"))
    )
    (net (code "81") (name "unconnected-(U4-CAP2_NC-Pad47)") (class "Default")
      (node (ref "U4") (pin "47") (pinfunction "CAP2_NC_47") (pintype "passive+no_connect"))
    )
    (net (code "82") (name "unconnected-(U4-VDD_SDIO_NC-Pad26)") (class "Default")
      (node (ref "U4") (pin "26") (pinfunction "VDD_SDIO_NC_26") (pintype "passive+no_connect"))
    )
    (net (code "83") (name "unconnected-(U4-XTAL_N_NC-Pad44)") (class "Default")
      (node (ref "U4") (pin "44") (pinfunction "XTAL_N_NC_44") (pintype "passive+no_connect"))
    )
    (net (code "84") (name "unconnected-(U4-XTAL_P_NC-Pad45)") (class "Default")
      (node (ref "U4") (pin "45") (pinfunction "XTAL_P_NC_45") (pintype "passive+no_connect"))
    )
    (net (code "85") (name "unconnected-(U5-AUX_CL-Pad7)") (class "Default")
      (node (ref "U5") (pin "7") (pinfunction "AUX_CL_7") (pintype "passive"))
    )
    (net (code "86") (name "unconnected-(U5-AUX_DA-Pad6)") (class "Default")
      (node (ref "U5") (pin "6") (pinfunction "AUX_DA_6") (pintype "passive"))
    )
    (net (code "87") (name "unconnected-(U5-NC-Pad2)") (class "Default")
      (node (ref "U5") (pin "2") (pinfunction "NC_2") (pintype "passive"))
    )
    (net (code "88") (name "unconnected-(U5-NC-Pad3)") (class "Default")
      (node (ref "U5") (pin "3") (pinfunction "NC_3") (pintype "passive"))
    )
    (net (code "89") (name "unconnected-(U5-NC-Pad4)") (class "Default")
      (node (ref "U5") (pin "4") (pinfunction "NC_4") (pintype "passive"))
    )
    (net (code "90") (name "unconnected-(U5-NC-Pad5)") (class "Default")
      (node (ref "U5") (pin "5") (pinfunction "NC_5") (pintype "passive"))
    )
    (net (code "91") (name "unconnected-(U5-NC-Pad14)") (class "Default")
      (node (ref "U5") (pin "14") (pinfunction "NC_14") (pintype "passive"))
    )
    (net (code "92") (name "unconnected-(U5-NC-Pad15)") (class "Default")
      (node (ref "U5") (pin "15") (pinfunction "NC_15") (pintype "passive"))
    )
    (net (code "93") (name "unconnected-(U5-NC-Pad16)") (class "Default")
      (node (ref "U5") (pin "16") (pinfunction "NC_16") (pintype "passive"))
    )
    (net (code "94") (name "unconnected-(U5-NC-Pad17)") (class "Default")
      (node (ref "U5") (pin "17") (pinfunction "NC_17") (pintype "passive"))
    )
    (net (code "95") (name "unconnected-(U5-RESV-Pad19)") (class "Default")
      (node (ref "U5") (pin "19") (pinfunction "RESV_19") (pintype "passive"))
    )
    (net (code "96") (name "unconnected-(U5-RESV-Pad21)") (class "Default")
      (node (ref "U5") (pin "21") (pinfunction "RESV_21") (pintype "passive"))
    )
    (net (code "97") (name "unconnected-(U5-RESV-Pad22)") (class "Default")
      (node (ref "U5") (pin "22") (pinfunction "RESV_22") (pintype "passive"))
    )
    (net (code "98") (name "unconnected-(USB1-SBU1-PadA8)") (class "Default")
      (node (ref "USB1") (pin "A8") (pinfunction "SBU1_A8") (pintype "passive"))
    )
    (net (code "99") (name "unconnected-(USB1-SBU2-PadB8)") (class "Default")
      (node (ref "USB1") (pin "B8") (pinfunction "SBU2_B8") (pintype "passive"))
    )
  )
)
